# 5VBoost.net
KiCad netlist of a schematic drawn in Altium Designer
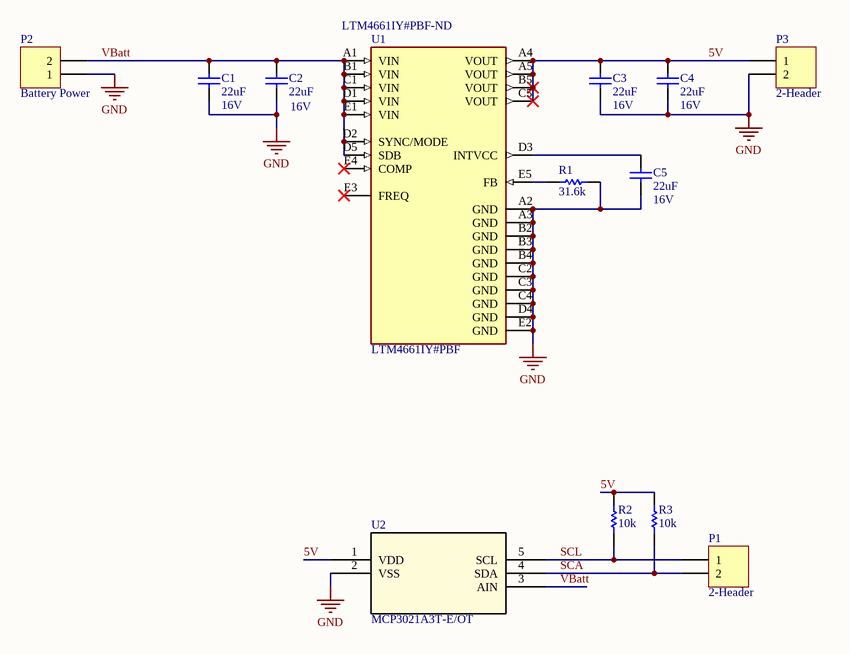
[diagram p0: 5VBoost.SchDoc]

(export (version "E")
  (design (tool "Eeschema 10.0.6"))
  (components
    (comp (ref "C1")
      (value "22uF")
      (footprint "1608[0603]")
      (description "Capacitor")
      (fields (field (name "ALTIUM_VALUE") "16V") (field (name "PUBLISHER") "Altium Limited"))
      (libsource (lib "Miscellaneous Devices") (part "Cap"))
    )
    (comp (ref "C2")
      (value "22uF")
      (footprint "1608[0603]")
      (description "Capacitor")
      (fields (field (name "ALTIUM_VALUE") "16V") (field (name "PUBLISHER") "Altium Limited"))
      (libsource (lib "Miscellaneous Devices") (part "Cap"))
    )
    (comp (ref "C3")
      (value "22uF")
      (footprint "1608[0603]")
      (description "Capacitor")
      (fields (field (name "ALTIUM_VALUE") "16V") (field (name "PUBLISHER") "Altium Limited"))
      (libsource (lib "Miscellaneous Devices") (part "Cap"))
    )
    (comp (ref "C4")
      (value "22uF")
      (footprint "1608[0603]")
      (description "Capacitor")
      (fields (field (name "ALTIUM_VALUE") "16V") (field (name "PUBLISHER") "Altium Limited"))
      (libsource (lib "Miscellaneous Devices") (part "Cap"))
    )
    (comp (ref "C5")
      (value "22uF")
      (footprint "1608[0603]")
      (description "Capacitor")
      (fields (field (name "ALTIUM_VALUE") "16V") (field (name "PUBLISHER") "Altium Limited"))
      (libsource (lib "Miscellaneous Devices") (part "Cap"))
    )
    (comp (ref "P1")
      (value "2-Header")
      (footprint "HDR1X2")
      (description "Header, 2-Pin")
      (fields (field (name "PUBLISHER") "Altium Limited"))
      (libsource (lib "") (part "Header 2_1"))
    )
    (comp (ref "P2")
      (value "Battery Power")
      (footprint "xt30 right angle")
      (description "Header, 2-Pin")
      (fields (field (name "PUBLISHER") "Altium Limited"))
      (libsource (lib "Miscellaneous Connectors") (part "Header 2"))
    )
    (comp (ref "P3")
      (value "2-Header")
      (footprint "HDR1X2")
      (description "Header, 2-Pin")
      (fields (field (name "PUBLISHER") "Altium Limited"))
      (libsource (lib "") (part "Header 2_1"))
    )
    (comp (ref "R1")
      (value "31.6k")
      (footprint "1608[0603]")
      (description "Resistor")
      (fields (field (name "PUBLISHER") "Altium Limited"))
      (libsource (lib "Miscellaneous Devices") (part "Res1"))
    )
    (comp (ref "R2")
      (value "10k")
      (footprint "1608[0603]")
      (description "Resistor")
      (fields (field (name "PUBLISHER") "Altium Limited"))
      (libsource (lib "Miscellaneous Devices") (part "Res1"))
    )
    (comp (ref "R3")
      (value "10k")
      (footprint "1608[0603]")
      (description "Resistor")
      (fields (field (name "PUBLISHER") "Altium Limited"))
      (libsource (lib "Miscellaneous Devices") (part "Res1"))
    )
    (comp (ref "U1")
      (value "LTM4661IY#PBF")
      (footprint "BGA25C127P5X5_625X625X262N")
      (description "Conv DC-DC 0.7V to 5.5V Step Up Single-Out 2.5V to 15V 2A uModule 25-Pin BGA Tray")
      (fields (field (name "MF") "Analog Devices") (field (name "SUPPLIER PART NUMBER 1") "LTM4661IY#PBF-ND"))
      (libsource (lib "LTM4661IY_PBF") (part "LTM4661IY#PBF"))
    )
    (comp (ref "U2")
      (value "MCP3021A3T-E/OT")
      (footprint "SOT-23-5_MC_MCH")
      (description "No Description Available")
      (fields (field (name "COPYRIGHT") "Copyright (C) 2018 Accelerated Designs. All rights reserved"))
      (libsource (lib "2020-09-11_15-45-06") (part "MCP3021A3T-E/OT"))
    )
  )
  (nets
    (net (code "1") (name "/5V") (class "Default")
      (node (ref "C3") (pin "2") (pinfunction "2_2") (pintype "passive"))
      (node (ref "C4") (pin "2") (pinfunction "2_2") (pintype "passive"))
      (node (ref "P3") (pin "1") (pinfunction "1_1") (pintype "passive"))
      (node (ref "R2") (pin "2") (pinfunction "2_2") (pintype "passive"))
      (node (ref "R3") (pin "2") (pinfunction "2_2") (pintype "passive"))
      (node (ref "U1") (pin "A4") (pinfunction "VOUT_A4") (pintype "output"))
      (node (ref "U1") (pin "A5") (pinfunction "VOUT_A5") (pintype "output"))
      (node (ref "U1") (pin "B5") (pinfunction "VOUT_B5") (pintype "output"))
      (node (ref "U1") (pin "C5") (pinfunction "VOUT_C5") (pintype "output"))
      (node (ref "U2") (pin "1") (pinfunction "VDD_1") (pintype "passive"))
    )
    (net (code "2") (name "/SCA") (class "Default")
      (node (ref "P1") (pin "2") (pinfunction "2_2") (pintype "passive"))
      (node (ref "R3") (pin "1") (pinfunction "1_1") (pintype "passive"))
      (node (ref "U2") (pin "4") (pinfunction "SDA_4") (pintype "passive"))
    )
    (net (code "3") (name "/SCL") (class "Default")
      (node (ref "P1") (pin "1") (pinfunction "1_1") (pintype "passive"))
      (node (ref "R2") (pin "1") (pinfunction "1_1") (pintype "passive"))
      (node (ref "U2") (pin "5") (pinfunction "SCL_5") (pintype "passive"))
    )
    (net (code "4") (name "/VBatt") (class "Default")
      (node (ref "C1") (pin "2") (pinfunction "2_2") (pintype "passive"))
      (node (ref "C2") (pin "2") (pinfunction "2_2") (pintype "passive"))
      (node (ref "P2") (pin "2") (pinfunction "2_2") (pintype "passive"))
      (node (ref "U1") (pin "A1") (pinfunction "VIN_A1") (pintype "input"))
      (node (ref "U1") (pin "B1") (pinfunction "VIN_B1") (pintype "input"))
      (node (ref "U1") (pin "C1") (pinfunction "VIN_C1") (pintype "input"))
      (node (ref "U1") (pin "D1") (pinfunction "VIN_D1") (pintype "input"))
      (node (ref "U1") (pin "D2") (pinfunction "SYNC/MODE_D2") (pintype "input"))
      (node (ref "U1") (pin "D5") (pinfunction "SDB_D5") (pintype "input"))
      (node (ref "U1") (pin "E1") (pinfunction "VIN_E1") (pintype "input"))
      (node (ref "U2") (pin "3") (pinfunction "AIN_3") (pintype "passive"))
    )
    (net (code "5") (name "GND") (class "Default")
      (node (ref "C1") (pin "1") (pinfunction "1_1") (pintype "passive"))
      (node (ref "C2") (pin "1") (pinfunction "1_1") (pintype "passive"))
      (node (ref "C3") (pin "1") (pinfunction "1_1") (pintype "passive"))
      (node (ref "C4") (pin "1") (pinfunction "1_1") (pintype "passive"))
      (node (ref "C5") (pin "2") (pinfunction "2_2") (pintype "passive"))
      (node (ref "P2") (pin "1") (pinfunction "1_1") (pintype "passive"))
      (node (ref "P3") (pin "2") (pinfunction "2_2") (pintype "passive"))
      (node (ref "R1") (pin "1") (pinfunction "1_1") (pintype "passive"))
      (node (ref "U1") (pin "A2") (pinfunction "GND_A2") (pintype "power_in"))
      (node (ref "U1") (pin "A3") (pinfunction "GND_A3") (pintype "power_in"))
      (node (ref "U1") (pin "B2") (pinfunction "GND_B2") (pintype "power_in"))
      (node (ref "U1") (pin "B3") (pinfunction "GND_B3") (pintype "power_in"))
      (node (ref "U1") (pin "B4") (pinfunction "GND_B4") (pintype "power_in"))
      (node (ref "U1") (pin "C2") (pinfunction "GND_C2") (pintype "power_in"))
      (node (ref "U1") (pin "C3") (pinfunction "GND_C3") (pintype "power_in"))
      (node (ref "U1") (pin "C4") (pinfunction "GND_C4") (pintype "power_in"))
      (node (ref "U1") (pin "D4") (pinfunction "GND_D4") (pintype "power_in"))
      (node (ref "U1") (pin "E2") (pinfunction "GND_E2") (pintype "power_in"))
      (node (ref "U2") (pin "2") (pinfunction "VSS_2") (pintype "passive"))
    )
    (net (code "6") (name "Net-(U1-FB)") (class "Default")
      (node (ref "R1") (pin "2") (pinfunction "2_2") (pintype "passive"))
      (node (ref "U1") (pin "E5") (pinfunction "FB_E5") (pintype "input"))
    )
    (net (code "7") (name "Net-(U1-INTVCC)") (class "Default")
      (node (ref "C5") (pin "1") (pinfunction "1_1") (pintype "passive"))
      (node (ref "U1") (pin "D3") (pinfunction "INTVCC_D3") (pintype "output"))
    )
    (net (code "8") (name "unconnected-(U1-COMP-PadE4)") (class "Default")
      (node (ref "U1") (pin "E4") (pinfunction "COMP_E4") (pintype "input+no_connect"))
    )
    (net (code "9") (name "unconnected-(U1-FREQ-PadE3)") (class "Default")
      (node (ref "U1") (pin "E3") (pinfunction "FREQ_E3") (pintype "passive+no_connect"))
    )
  )
)
